# template.net
KiCad netlist of a schematic drawn in EAGLE
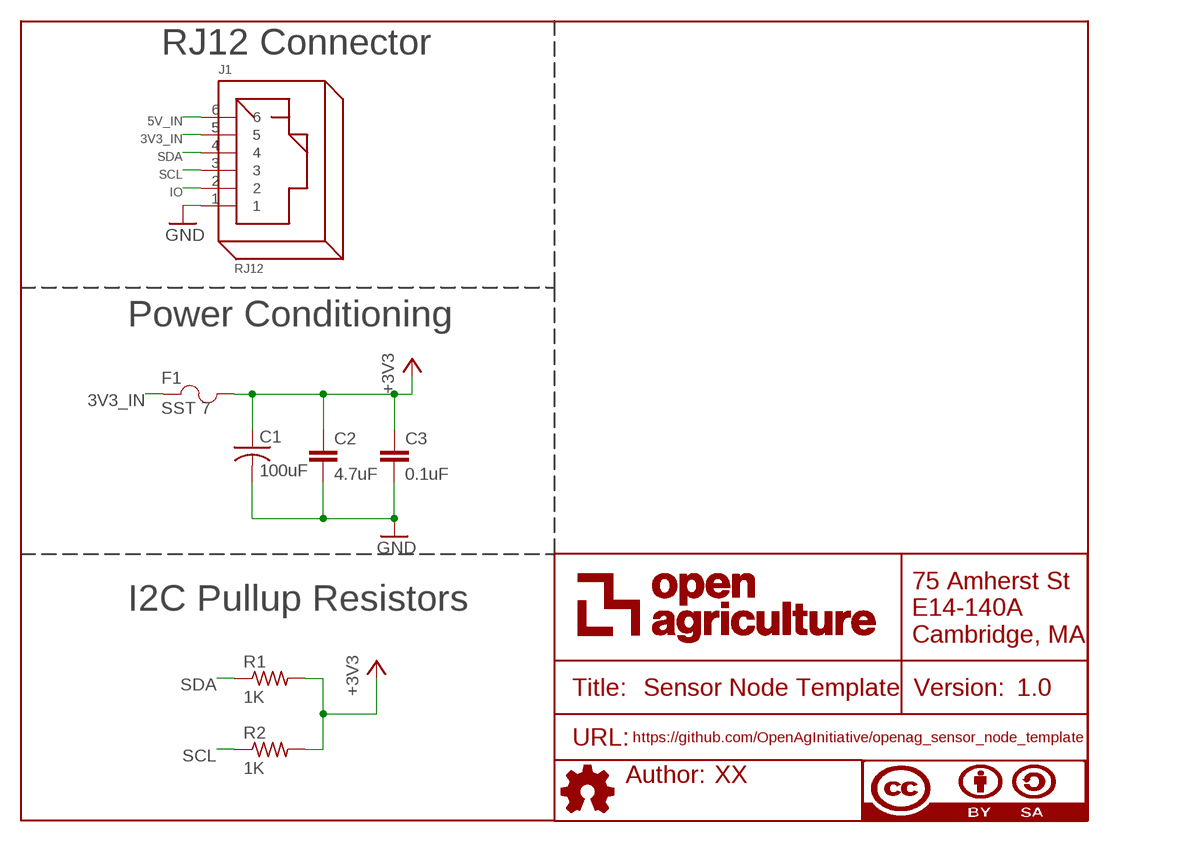
[diagram p0: schematic, sheet 1]

(export (version "E")
  (design (tool "Eeschema 10.0.6"))
  (components
    (comp (ref "C1")
      (value "100uF")
      (footprint "eagle-import:EEE-1HA101UP")
      (libsource (lib "eagle-import") (part "100UF-EEE-1HA101UP"))
    )
    (comp (ref "C2")
      (value "4.7uF")
      (footprint "eagle-import:C0805")
      (libsource (lib "eagle-import") (part "4.7UF-CL21A475KBQNNNE"))
    )
    (comp (ref "C3")
      (value "0.1uF")
      (footprint "eagle-import:C0603")
      (libsource (lib "eagle-import") (part "0.1UF-C0603C104K5RACTU"))
    )
    (comp (ref "F1")
      (value "SST 7")
      (footprint "eagle-import:SS")
      (libsource (lib "eagle-import") (part "SST_7"))
    )
    (comp (ref "FRAME1")
      (value "DOCFIELD")
      (footprint "eagle-import:DOCFIELD")
      (description "Sensor Node Template")
      (fields
        (field (name "TITLE") "Sensor Node Template")
        (field (name "URL") "https://github.com/OpenAgInitiative/openag_sensor_node_template")
        (field (name "AUTHOR") "XX")
      )
      (libsource (lib "eagle-import") (part "DOCFIELD"))
    )
    (comp (ref "J1")
      (value "RJ12")
      (footprint "eagle-import:RJ12")
      (libsource (lib "eagle-import") (part "A-2004-1-4-LP-N-R"))
    )
    (comp (ref "R1")
      (value "1K")
      (footprint "eagle-import:RC0603N")
      (libsource (lib "eagle-import") (part "1K-ERJ-PB3D1001V"))
    )
    (comp (ref "R2")
      (value "1K")
      (footprint "eagle-import:RC0603N")
      (libsource (lib "eagle-import") (part "1K-ERJ-PB3D1001V"))
    )
  )
  (nets
    (net (code "1") (name "+3V3") (class "Default")
      (node (ref "C1") (pin "+") (pinfunction "1(+)_+") (pintype "passive"))
      (node (ref "C2") (pin "1") (pinfunction "1_1") (pintype "passive"))
      (node (ref "C3") (pin "1") (pinfunction "1_1") (pintype "passive"))
      (node (ref "F1") (pin "2") (pinfunction "2_2") (pintype "passive"))
      (node (ref "R1") (pin "2") (pinfunction "2_2") (pintype "passive"))
      (node (ref "R2") (pin "2") (pinfunction "2_2") (pintype "passive"))
    )
    (net (code "2") (name "3V3_IN") (class "Default")
      (node (ref "F1") (pin "1") (pinfunction "1_1") (pintype "passive"))
      (node (ref "J1") (pin "5") (pinfunction "5_5") (pintype "bidirectional"))
    )
    (net (code "3") (name "5V_IN") (class "Default")
      (node (ref "J1") (pin "6") (pinfunction "6_6") (pintype "bidirectional"))
    )
    (net (code "4") (name "GND") (class "Default")
      (node (ref "C1") (pin "-") (pinfunction "2(-)_-") (pintype "passive"))
      (node (ref "C2") (pin "2") (pinfunction "2_2") (pintype "passive"))
      (node (ref "C3") (pin "2") (pinfunction "2_2") (pintype "passive"))
      (node (ref "J1") (pin "1") (pinfunction "1_1") (pintype "bidirectional"))
    )
    (net (code "5") (name "IO") (class "Default")
      (node (ref "J1") (pin "2") (pinfunction "2_2") (pintype "bidirectional"))
    )
    (net (code "6") (name "SCL") (class "Default")
      (node (ref "J1") (pin "3") (pinfunction "3_3") (pintype "bidirectional"))
      (node (ref "R2") (pin "1") (pinfunction "1_1") (pintype "passive"))
    )
    (net (code "7") (name "SDA") (class "Default")
      (node (ref "J1") (pin "4") (pinfunction "4_4") (pintype "bidirectional"))
      (node (ref "R1") (pin "1") (pinfunction "1_1") (pintype "passive"))
    )
  )
)
